# Reflectance.net
KiCad netlist of a schematic drawn in Altium Designer
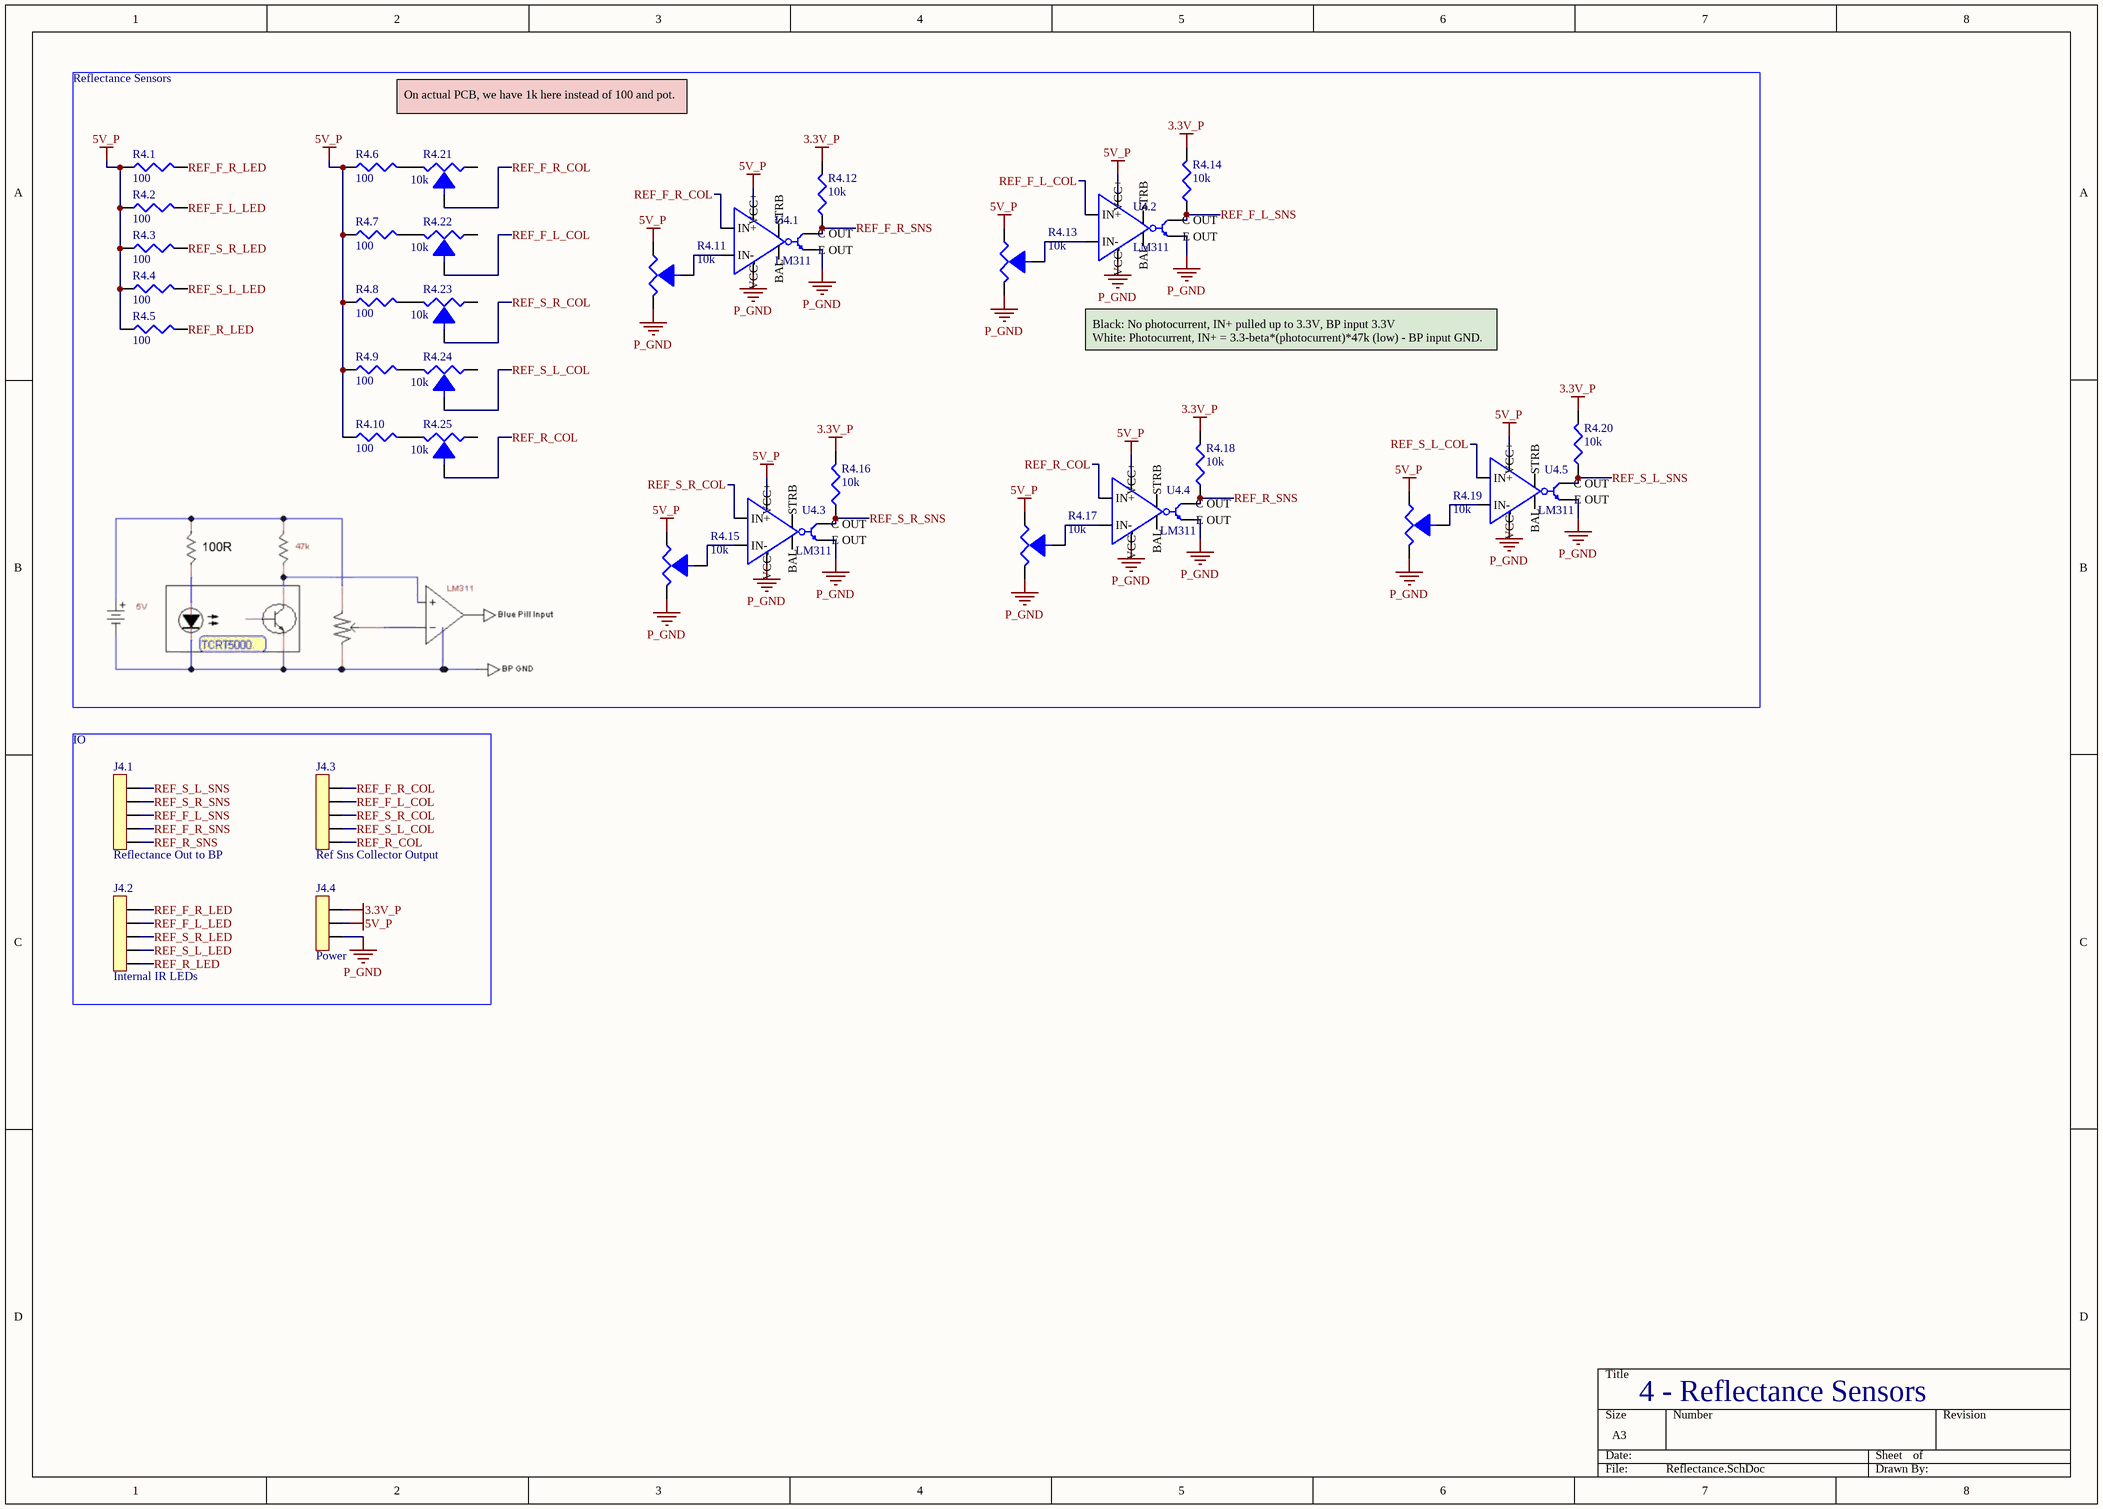
[diagram p0: Reflectance.SchDoc]

(export (version "E")
  (design (tool "Eeschema 10.0.6"))
  (components
    (comp (ref "J4.1")
      (value "Reflectance Out to BP")
      (footprint "5POS JST")
      (description "5pos Conn JST")
      (libsource (lib "SPICEBot_SchLib") (part "5pos Conn"))
    )
    (comp (ref "J4.2")
      (value "Internal IR LEDs")
      (footprint "5POS JST")
      (description "5pos Conn JST")
      (libsource (lib "SPICEBot_SchLib") (part "5pos Conn"))
    )
    (comp (ref "J4.3")
      (value "Ref Sns Collector Output")
      (footprint "5POS JST")
      (description "5pos Conn JST")
      (libsource (lib "SPICEBot_SchLib") (part "5pos Conn"))
    )
    (comp (ref "J4.4")
      (value "Power")
      (footprint "3pos JST")
      (description "3pos Conn")
      (libsource (lib "SPICEBot_SchLib") (part "3pos Conn"))
    )
    (comp (ref "R4.1")
      (value "100")
      (footprint "Res_Generic")
      (libsource (lib "SPICEBot_SchLib") (part "Res_Generic"))
    )
    (comp (ref "R4.2")
      (value "100")
      (footprint "Res_Generic")
      (libsource (lib "SPICEBot_SchLib") (part "Res_Generic"))
    )
    (comp (ref "R4.3")
      (value "100")
      (footprint "Res_Generic")
      (libsource (lib "SPICEBot_SchLib") (part "Res_Generic"))
    )
    (comp (ref "R4.4")
      (value "100")
      (footprint "Res_Generic")
      (libsource (lib "SPICEBot_SchLib") (part "Res_Generic"))
    )
    (comp (ref "R4.5")
      (value "100")
      (footprint "Res_Generic")
      (libsource (lib "SPICEBot_SchLib") (part "Res_Generic"))
    )
    (comp (ref "R4.6")
      (value "100")
      (footprint "Res_Generic")
      (libsource (lib "SPICEBot_SchLib") (part "Res_Generic"))
    )
    (comp (ref "R4.7")
      (value "100")
      (footprint "Res_Generic")
      (libsource (lib "SPICEBot_SchLib") (part "Res_Generic"))
    )
    (comp (ref "R4.8")
      (value "100")
      (footprint "Res_Generic")
      (libsource (lib "SPICEBot_SchLib") (part "Res_Generic"))
    )
    (comp (ref "R4.9")
      (value "100")
      (footprint "Res_Generic")
      (libsource (lib "SPICEBot_SchLib") (part "Res_Generic"))
    )
    (comp (ref "R4.10")
      (value "100")
      (footprint "Res_Generic")
      (libsource (lib "SPICEBot_SchLib") (part "Res_Generic"))
    )
    (comp (ref "R4.11")
      (value "10k")
      (footprint "Pot Generic")
      (libsource (lib "SPICEBot_SchLib") (part "Pot_Generic"))
    )
    (comp (ref "R4.12")
      (value "10k")
      (footprint "Res_Generic")
      (libsource (lib "SPICEBot_SchLib") (part "Res_Generic"))
    )
    (comp (ref "R4.13")
      (value "10k")
      (footprint "Pot Generic")
      (libsource (lib "SPICEBot_SchLib") (part "Pot_Generic"))
    )
    (comp (ref "R4.14")
      (value "10k")
      (footprint "Res_Generic")
      (libsource (lib "SPICEBot_SchLib") (part "Res_Generic"))
    )
    (comp (ref "R4.15")
      (value "10k")
      (footprint "Pot Generic")
      (libsource (lib "SPICEBot_SchLib") (part "Pot_Generic"))
    )
    (comp (ref "R4.16")
      (value "10k")
      (footprint "Res_Generic")
      (libsource (lib "SPICEBot_SchLib") (part "Res_Generic"))
    )
    (comp (ref "R4.17")
      (value "10k")
      (footprint "Pot Generic")
      (libsource (lib "SPICEBot_SchLib") (part "Pot_Generic"))
    )
    (comp (ref "R4.18")
      (value "10k")
      (footprint "Res_Generic")
      (libsource (lib "SPICEBot_SchLib") (part "Res_Generic"))
    )
    (comp (ref "R4.19")
      (value "10k")
      (footprint "Pot Generic")
      (libsource (lib "SPICEBot_SchLib") (part "Pot_Generic"))
    )
    (comp (ref "R4.20")
      (value "10k")
      (footprint "Res_Generic")
      (libsource (lib "SPICEBot_SchLib") (part "Res_Generic"))
    )
    (comp (ref "R4.21")
      (value "10k")
      (footprint "Pot Generic")
      (libsource (lib "SPICEBot_SchLib") (part "Pot_Generic"))
    )
    (comp (ref "R4.22")
      (value "10k")
      (footprint "Pot Generic")
      (libsource (lib "SPICEBot_SchLib") (part "Pot_Generic"))
    )
    (comp (ref "R4.23")
      (value "10k")
      (footprint "Pot Generic")
      (libsource (lib "SPICEBot_SchLib") (part "Pot_Generic"))
    )
    (comp (ref "R4.24")
      (value "10k")
      (footprint "Pot Generic")
      (libsource (lib "SPICEBot_SchLib") (part "Pot_Generic"))
    )
    (comp (ref "R4.25")
      (value "10k")
      (footprint "Pot Generic")
      (libsource (lib "SPICEBot_SchLib") (part "Pot_Generic"))
    )
    (comp (ref "U4.1")
      (value "LM311")
      (footprint "DIP8")
      (description "LM311 IC DIFF COMPARATOR STROBE 8-DIP")
      (libsource (lib "SPICEBot_SchLib") (part "LM311 Comparator"))
    )
    (comp (ref "U4.2")
      (value "LM311")
      (footprint "DIP8")
      (description "LM311 IC DIFF COMPARATOR STROBE 8-DIP")
      (libsource (lib "SPICEBot_SchLib") (part "LM311 Comparator"))
    )
    (comp (ref "U4.3")
      (value "LM311")
      (footprint "DIP8")
      (description "LM311 IC DIFF COMPARATOR STROBE 8-DIP")
      (libsource (lib "SPICEBot_SchLib") (part "LM311 Comparator"))
    )
    (comp (ref "U4.4")
      (value "LM311")
      (footprint "DIP8")
      (description "LM311 IC DIFF COMPARATOR STROBE 8-DIP")
      (libsource (lib "SPICEBot_SchLib") (part "LM311 Comparator"))
    )
    (comp (ref "U4.5")
      (value "LM311")
      (footprint "DIP8")
      (description "LM311 IC DIFF COMPARATOR STROBE 8-DIP")
      (libsource (lib "SPICEBot_SchLib") (part "LM311 Comparator"))
    )
  )
  (nets
    (net (code "1") (name "/REF_F_L_COL") (class "Default")
      (node (ref "J4.3") (pin "3") (pinfunction "3_3") (pintype "passive"))
      (node (ref "R4.22") (pin "2") (pinfunction "2_2") (pintype "passive"))
      (node (ref "U4.2") (pin "2") (pinfunction "IN+_2") (pintype "passive"))
    )
    (net (code "2") (name "/REF_F_L_LED") (class "Default")
      (node (ref "J4.2") (pin "3") (pinfunction "3_3") (pintype "passive"))
      (node (ref "R4.2") (pin "2") (pinfunction "2_2") (pintype "passive"))
    )
    (net (code "3") (name "/REF_F_L_SNS") (class "Default")
      (node (ref "J4.1") (pin "2") (pinfunction "2_2") (pintype "passive"))
      (node (ref "R4.14") (pin "1") (pinfunction "1_1") (pintype "passive"))
      (node (ref "U4.2") (pin "7") (pinfunction "C_OUT_7") (pintype "passive"))
    )
    (net (code "4") (name "/REF_F_R_COL") (class "Default")
      (node (ref "J4.3") (pin "4") (pinfunction "4_4") (pintype "passive"))
      (node (ref "R4.21") (pin "2") (pinfunction "2_2") (pintype "passive"))
      (node (ref "U4.1") (pin "2") (pinfunction "IN+_2") (pintype "passive"))
    )
    (net (code "5") (name "/REF_F_R_LED") (class "Default")
      (node (ref "J4.2") (pin "4") (pinfunction "4_4") (pintype "passive"))
      (node (ref "R4.1") (pin "2") (pinfunction "2_2") (pintype "passive"))
    )
    (net (code "6") (name "/REF_F_R_SNS") (class "Default")
      (node (ref "J4.1") (pin "1") (pinfunction "1_1") (pintype "passive"))
      (node (ref "R4.12") (pin "1") (pinfunction "1_1") (pintype "passive"))
      (node (ref "U4.1") (pin "7") (pinfunction "C_OUT_7") (pintype "passive"))
    )
    (net (code "7") (name "/REF_R_COL") (class "Default")
      (node (ref "J4.3") (pin "5") (pinfunction "5_5") (pintype "passive"))
      (node (ref "R4.25") (pin "2") (pinfunction "2_2") (pintype "passive"))
      (node (ref "U4.4") (pin "2") (pinfunction "IN+_2") (pintype "passive"))
    )
    (net (code "8") (name "/REF_R_LED") (class "Default")
      (node (ref "J4.2") (pin "5") (pinfunction "5_5") (pintype "passive"))
      (node (ref "R4.5") (pin "2") (pinfunction "2_2") (pintype "passive"))
    )
    (net (code "9") (name "/REF_R_SNS") (class "Default")
      (node (ref "J4.1") (pin "5") (pinfunction "5_5") (pintype "passive"))
      (node (ref "R4.18") (pin "1") (pinfunction "1_1") (pintype "passive"))
      (node (ref "U4.4") (pin "7") (pinfunction "C_OUT_7") (pintype "passive"))
    )
    (net (code "10") (name "/REF_S_L_COL") (class "Default")
      (node (ref "J4.3") (pin "1") (pinfunction "1_1") (pintype "passive"))
      (node (ref "R4.24") (pin "2") (pinfunction "2_2") (pintype "passive"))
      (node (ref "U4.5") (pin "2") (pinfunction "IN+_2") (pintype "passive"))
    )
    (net (code "11") (name "/REF_S_L_LED") (class "Default")
      (node (ref "J4.2") (pin "1") (pinfunction "1_1") (pintype "passive"))
      (node (ref "R4.4") (pin "2") (pinfunction "2_2") (pintype "passive"))
    )
    (net (code "12") (name "/REF_S_L_SNS") (class "Default")
      (node (ref "J4.1") (pin "4") (pinfunction "4_4") (pintype "passive"))
      (node (ref "R4.20") (pin "1") (pinfunction "1_1") (pintype "passive"))
      (node (ref "U4.5") (pin "7") (pinfunction "C_OUT_7") (pintype "passive"))
    )
    (net (code "13") (name "/REF_S_R_COL") (class "Default")
      (node (ref "J4.3") (pin "2") (pinfunction "2_2") (pintype "passive"))
      (node (ref "R4.23") (pin "2") (pinfunction "2_2") (pintype "passive"))
      (node (ref "U4.3") (pin "2") (pinfunction "IN+_2") (pintype "passive"))
    )
    (net (code "14") (name "/REF_S_R_LED") (class "Default")
      (node (ref "J4.2") (pin "2") (pinfunction "2_2") (pintype "passive"))
      (node (ref "R4.3") (pin "2") (pinfunction "2_2") (pintype "passive"))
    )
    (net (code "15") (name "/REF_S_R_SNS") (class "Default")
      (node (ref "J4.1") (pin "3") (pinfunction "3_3") (pintype "passive"))
      (node (ref "R4.16") (pin "1") (pinfunction "1_1") (pintype "passive"))
      (node (ref "U4.3") (pin "7") (pinfunction "C_OUT_7") (pintype "passive"))
    )
    (net (code "16") (name "3.3V_P") (class "Default")
      (node (ref "J4.4") (pin "3") (pinfunction "3_3") (pintype "passive"))
      (node (ref "R4.12") (pin "2") (pinfunction "2_2") (pintype "passive"))
      (node (ref "R4.14") (pin "2") (pinfunction "2_2") (pintype "passive"))
      (node (ref "R4.16") (pin "2") (pinfunction "2_2") (pintype "passive"))
      (node (ref "R4.18") (pin "2") (pinfunction "2_2") (pintype "passive"))
      (node (ref "R4.20") (pin "2") (pinfunction "2_2") (pintype "passive"))
    )
    (net (code "17") (name "5V_P") (class "Default")
      (node (ref "J4.4") (pin "2") (pinfunction "2_2") (pintype "passive"))
      (node (ref "R4.1") (pin "1") (pinfunction "1_1") (pintype "passive"))
      (node (ref "R4.10") (pin "1") (pinfunction "1_1") (pintype "passive"))
      (node (ref "R4.11") (pin "3") (pinfunction "3_3") (pintype "passive"))
      (node (ref "R4.13") (pin "3") (pinfunction "3_3") (pintype "passive"))
      (node (ref "R4.15") (pin "3") (pinfunction "3_3") (pintype "passive"))
      (node (ref "R4.17") (pin "3") (pinfunction "3_3") (pintype "passive"))
      (node (ref "R4.19") (pin "3") (pinfunction "3_3") (pintype "passive"))
      (node (ref "R4.2") (pin "1") (pinfunction "1_1") (pintype "passive"))
      (node (ref "R4.3") (pin "1") (pinfunction "1_1") (pintype "passive"))
      (node (ref "R4.4") (pin "1") (pinfunction "1_1") (pintype "passive"))
      (node (ref "R4.5") (pin "1") (pinfunction "1_1") (pintype "passive"))
      (node (ref "R4.6") (pin "1") (pinfunction "1_1") (pintype "passive"))
      (node (ref "R4.7") (pin "1") (pinfunction "1_1") (pintype "passive"))
      (node (ref "R4.8") (pin "1") (pinfunction "1_1") (pintype "passive"))
      (node (ref "R4.9") (pin "1") (pinfunction "1_1") (pintype "passive"))
      (node (ref "U4.1") (pin "8") (pinfunction "VCC+_8") (pintype "passive"))
      (node (ref "U4.2") (pin "8") (pinfunction "VCC+_8") (pintype "passive"))
      (node (ref "U4.3") (pin "8") (pinfunction "VCC+_8") (pintype "passive"))
      (node (ref "U4.4") (pin "8") (pinfunction "VCC+_8") (pintype "passive"))
      (node (ref "U4.5") (pin "8") (pinfunction "VCC+_8") (pintype "passive"))
    )
    (net (code "18") (name "Net-(R4.10-Pad2)") (class "Default")
      (node (ref "R4.10") (pin "2") (pinfunction "2_2") (pintype "passive"))
      (node (ref "R4.25") (pin "1") (pinfunction "1_1") (pintype "passive"))
    )
    (net (code "19") (name "Net-(R4.21-Pad1)") (class "Default")
      (node (ref "R4.21") (pin "1") (pinfunction "1_1") (pintype "passive"))
      (node (ref "R4.6") (pin "2") (pinfunction "2_2") (pintype "passive"))
    )
    (net (code "20") (name "Net-(R4.22-Pad1)") (class "Default")
      (node (ref "R4.22") (pin "1") (pinfunction "1_1") (pintype "passive"))
      (node (ref "R4.7") (pin "2") (pinfunction "2_2") (pintype "passive"))
    )
    (net (code "21") (name "Net-(R4.23-Pad1)") (class "Default")
      (node (ref "R4.23") (pin "1") (pinfunction "1_1") (pintype "passive"))
      (node (ref "R4.8") (pin "2") (pinfunction "2_2") (pintype "passive"))
    )
    (net (code "22") (name "Net-(R4.24-Pad1)") (class "Default")
      (node (ref "R4.24") (pin "1") (pinfunction "1_1") (pintype "passive"))
      (node (ref "R4.9") (pin "2") (pinfunction "2_2") (pintype "passive"))
    )
    (net (code "23") (name "Net-(U4.1-IN-)") (class "Default")
      (node (ref "R4.11") (pin "2") (pinfunction "2_2") (pintype "passive"))
      (node (ref "U4.1") (pin "3") (pinfunction "IN-_3") (pintype "passive"))
    )
    (net (code "24") (name "Net-(U4.2-IN-)") (class "Default")
      (node (ref "R4.13") (pin "2") (pinfunction "2_2") (pintype "passive"))
      (node (ref "U4.2") (pin "3") (pinfunction "IN-_3") (pintype "passive"))
    )
    (net (code "25") (name "Net-(U4.3-IN-)") (class "Default")
      (node (ref "R4.15") (pin "2") (pinfunction "2_2") (pintype "passive"))
      (node (ref "U4.3") (pin "3") (pinfunction "IN-_3") (pintype "passive"))
    )
    (net (code "26") (name "Net-(U4.4-IN-)") (class "Default")
      (node (ref "R4.17") (pin "2") (pinfunction "2_2") (pintype "passive"))
      (node (ref "U4.4") (pin "3") (pinfunction "IN-_3") (pintype "passive"))
    )
    (net (code "27") (name "Net-(U4.5-IN-)") (class "Default")
      (node (ref "R4.19") (pin "2") (pinfunction "2_2") (pintype "passive"))
      (node (ref "U4.5") (pin "3") (pinfunction "IN-_3") (pintype "passive"))
    )
    (net (code "28") (name "P_GND") (class "Default")
      (node (ref "J4.4") (pin "1") (pinfunction "1_1") (pintype "passive"))
      (node (ref "R4.11") (pin "1") (pinfunction "1_1") (pintype "passive"))
      (node (ref "R4.13") (pin "1") (pinfunction "1_1") (pintype "passive"))
      (node (ref "R4.15") (pin "1") (pinfunction "1_1") (pintype "passive"))
      (node (ref "R4.17") (pin "1") (pinfunction "1_1") (pintype "passive"))
      (node (ref "R4.19") (pin "1") (pinfunction "1_1") (pintype "passive"))
      (node (ref "U4.1") (pin "1") (pinfunction "E_OUT_1") (pintype "passive"))
      (node (ref "U4.1") (pin "4") (pinfunction "VCC-_4") (pintype "passive"))
      (node (ref "U4.2") (pin "1") (pinfunction "E_OUT_1") (pintype "passive"))
      (node (ref "U4.2") (pin "4") (pinfunction "VCC-_4") (pintype "passive"))
      (node (ref "U4.3") (pin "1") (pinfunction "E_OUT_1") (pintype "passive"))
      (node (ref "U4.3") (pin "4") (pinfunction "VCC-_4") (pintype "passive"))
      (node (ref "U4.4") (pin "1") (pinfunction "E_OUT_1") (pintype "passive"))
      (node (ref "U4.4") (pin "4") (pinfunction "VCC-_4") (pintype "passive"))
      (node (ref "U4.5") (pin "1") (pinfunction "E_OUT_1") (pintype "passive"))
      (node (ref "U4.5") (pin "4") (pinfunction "VCC-_4") (pintype "passive"))
    )
    (net (code "29") (name "unconnected-(R4.21-Pad3)") (class "Default")
      (node (ref "R4.21") (pin "3") (pinfunction "3_3") (pintype "passive"))
    )
    (net (code "30") (name "unconnected-(R4.22-Pad3)") (class "Default")
      (node (ref "R4.22") (pin "3") (pinfunction "3_3") (pintype "passive"))
    )
    (net (code "31") (name "unconnected-(R4.23-Pad3)") (class "Default")
      (node (ref "R4.23") (pin "3") (pinfunction "3_3") (pintype "passive"))
    )
    (net (code "32") (name "unconnected-(R4.24-Pad3)") (class "Default")
      (node (ref "R4.24") (pin "3") (pinfunction "3_3") (pintype "passive"))
    )
    (net (code "33") (name "unconnected-(R4.25-Pad3)") (class "Default")
      (node (ref "R4.25") (pin "3") (pinfunction "3_3") (pintype "passive"))
    )
    (net (code "34") (name "unconnected-(U4.1-BAL-Pad5)") (class "Default")
      (node (ref "U4.1") (pin "5") (pinfunction "BAL_5") (pintype "passive"))
    )
    (net (code "35") (name "unconnected-(U4.1-STRB-Pad6)") (class "Default")
      (node (ref "U4.1") (pin "6") (pinfunction "STRB_6") (pintype "passive"))
    )
    (net (code "36") (name "unconnected-(U4.2-BAL-Pad5)") (class "Default")
      (node (ref "U4.2") (pin "5") (pinfunction "BAL_5") (pintype "passive"))
    )
    (net (code "37") (name "unconnected-(U4.2-STRB-Pad6)") (class "Default")
      (node (ref "U4.2") (pin "6") (pinfunction "STRB_6") (pintype "passive"))
    )
    (net (code "38") (name "unconnected-(U4.3-BAL-Pad5)") (class "Default")
      (node (ref "U4.3") (pin "5") (pinfunction "BAL_5") (pintype "passive"))
    )
    (net (code "39") (name "unconnected-(U4.3-STRB-Pad6)") (class "Default")
      (node (ref "U4.3") (pin "6") (pinfunction "STRB_6") (pintype "passive"))
    )
    (net (code "40") (name "unconnected-(U4.4-BAL-Pad5)") (class "Default")
      (node (ref "U4.4") (pin "5") (pinfunction "BAL_5") (pintype "passive"))
    )
    (net (code "41") (name "unconnected-(U4.4-STRB-Pad6)") (class "Default")
      (node (ref "U4.4") (pin "6") (pinfunction "STRB_6") (pintype "passive"))
    )
    (net (code "42") (name "unconnected-(U4.5-BAL-Pad5)") (class "Default")
      (node (ref "U4.5") (pin "5") (pinfunction "BAL_5") (pintype "passive"))
    )
    (net (code "43") (name "unconnected-(U4.5-STRB-Pad6)") (class "Default")
      (node (ref "U4.5") (pin "6") (pinfunction "STRB_6") (pintype "passive"))
    )
  )
)
